# golden_arduino.net
KiCad netlist of a schematic drawn in Altium Designer
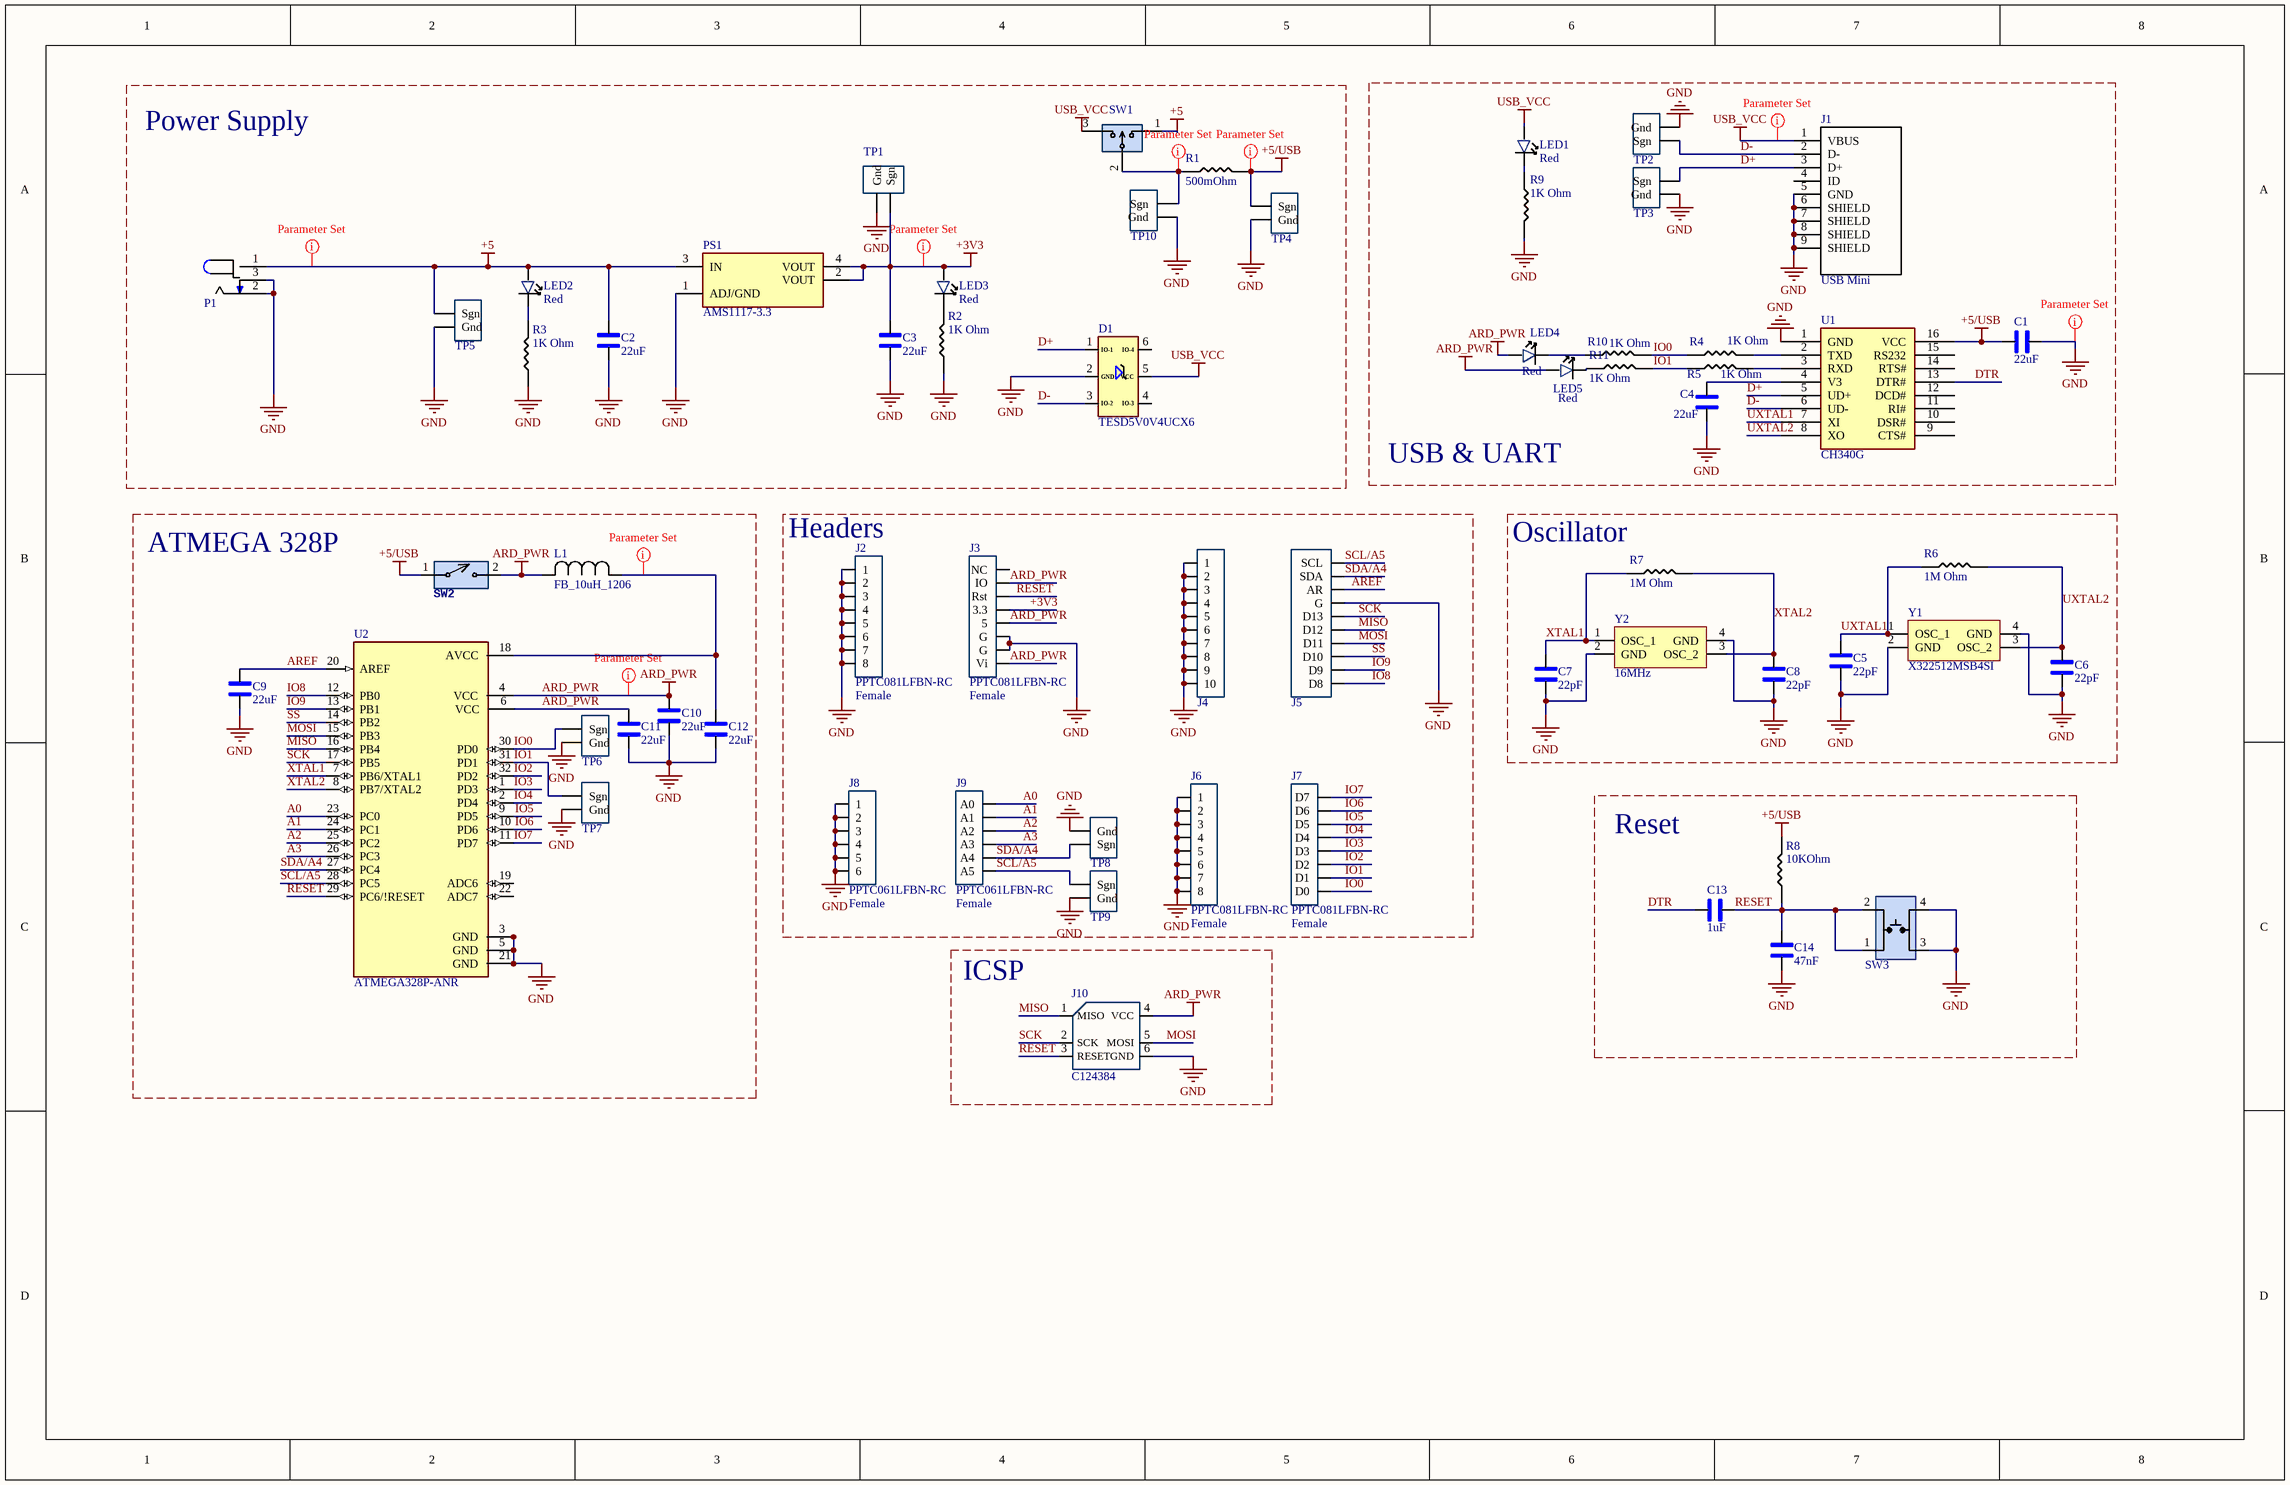
[diagram p0: golden_arduino.SchDoc]

(export (version "E")
  (design (tool "Eeschema 10.0.6"))
  (components
    (comp (ref "C1")
      (value "22uF")
      (footprint "1206_Passive_Capacitor")
      (description "22uF ±10% 25V X5R 1206 Multilayer Ceramic Capacitors MLCC - SMD/SMT RoHS")
      (fields (field (name "MFR PART #") "CL31A226KAHNNNE") (field (name "LCSC PART#") "C12891"))
      (libsource (lib "ECEN5730Lib_2023_05_DS") (part "C_22uF_1206"))
    )
    (comp (ref "C2")
      (value "22uF")
      (footprint "1206_Passive_Capacitor")
      (description "22uF ±10% 25V X5R 1206 Multilayer Ceramic Capacitors MLCC - SMD/SMT RoHS")
      (fields (field (name "MFR PART #") "CL31A226KAHNNNE") (field (name "LCSC PART#") "C12891"))
      (libsource (lib "ECEN5730Lib_2023_05_DS") (part "C_22uF_1206"))
    )
    (comp (ref "C3")
      (value "22uF")
      (footprint "1206_Passive_Capacitor")
      (description "22uF ±10% 25V X5R 1206 Multilayer Ceramic Capacitors MLCC - SMD/SMT RoHS")
      (fields (field (name "MFR PART #") "CL31A226KAHNNNE") (field (name "LCSC PART#") "C12891"))
      (libsource (lib "ECEN5730Lib_2023_05_DS") (part "C_22uF_1206"))
    )
    (comp (ref "C4")
      (value "22uF")
      (footprint "1206_Passive_Capacitor")
      (description "22uF ±10% 25V X5R 1206 Multilayer Ceramic Capacitors MLCC - SMD/SMT RoHS")
      (fields (field (name "MFR PART #") "CL31A226KAHNNNE") (field (name "LCSC PART#") "C12891"))
      (libsource (lib "ECEN5730Lib_2023_05_DS") (part "C_22uF_1206"))
    )
    (comp (ref "C5")
      (value "22pF")
      (footprint "1206_Passive_Capacitor")
      (description "22pF ±5% 1kV C0G 1206 Multilayer Ceramic Capacitors MLCC - SMD/SMT RoHS")
      (fields (field (name "LCSC PART#") "C107174") (field (name "MFR PART #") "CC1206JKNPOCBN220"))
      (libsource (lib "ECEN5730Lib_2023_05_DS") (part "C_22pF_1206"))
    )
    (comp (ref "C6")
      (value "22pF")
      (footprint "1206_Passive_Capacitor")
      (description "22pF ±5% 1kV C0G 1206 Multilayer Ceramic Capacitors MLCC - SMD/SMT RoHS")
      (fields (field (name "LCSC PART#") "C107174") (field (name "MFR PART #") "CC1206JKNPOCBN220"))
      (libsource (lib "ECEN5730Lib_2023_05_DS") (part "C_22pF_1206"))
    )
    (comp (ref "C7")
      (value "22pF")
      (footprint "1206_Passive_Capacitor")
      (description "22pF ±5% 1kV C0G 1206 Multilayer Ceramic Capacitors MLCC - SMD/SMT RoHS")
      (fields (field (name "LCSC PART#") "C107174") (field (name "MFR PART #") "CC1206JKNPOCBN220"))
      (libsource (lib "ECEN5730Lib_2023_05_DS") (part "C_22pF_1206"))
    )
    (comp (ref "C8")
      (value "22pF")
      (footprint "1206_Passive_Capacitor")
      (description "22pF ±5% 1kV C0G 1206 Multilayer Ceramic Capacitors MLCC - SMD/SMT RoHS")
      (fields (field (name "LCSC PART#") "C107174") (field (name "MFR PART #") "CC1206JKNPOCBN220"))
      (libsource (lib "ECEN5730Lib_2023_05_DS") (part "C_22pF_1206"))
    )
    (comp (ref "C9")
      (value "22uF")
      (footprint "1206_Passive_Capacitor")
      (description "22uF ±10% 25V X5R 1206 Multilayer Ceramic Capacitors MLCC - SMD/SMT RoHS")
      (fields (field (name "MFR PART #") "CL31A226KAHNNNE") (field (name "LCSC PART#") "C12891"))
      (libsource (lib "ECEN5730Lib_2023_05_DS") (part "C_22uF_1206"))
    )
    (comp (ref "C10")
      (value "22uF")
      (footprint "1206_Passive_Capacitor")
      (description "22uF ±10% 25V X5R 1206 Multilayer Ceramic Capacitors MLCC - SMD/SMT RoHS")
      (fields (field (name "MFR PART #") "CL31A226KAHNNNE") (field (name "LCSC PART#") "C12891"))
      (libsource (lib "ECEN5730Lib_2023_05_DS") (part "C_22uF_1206"))
    )
    (comp (ref "C11")
      (value "22uF")
      (footprint "1206_Passive_Capacitor")
      (description "22uF ±10% 25V X5R 1206 Multilayer Ceramic Capacitors MLCC - SMD/SMT RoHS")
      (fields (field (name "MFR PART #") "CL31A226KAHNNNE") (field (name "LCSC PART#") "C12891"))
      (libsource (lib "ECEN5730Lib_2023_05_DS") (part "C_22uF_1206"))
    )
    (comp (ref "C12")
      (value "22uF")
      (footprint "1206_Passive_Capacitor")
      (description "22uF ±10% 25V X5R 1206 Multilayer Ceramic Capacitors MLCC - SMD/SMT RoHS")
      (fields (field (name "MFR PART #") "CL31A226KAHNNNE") (field (name "LCSC PART#") "C12891"))
      (libsource (lib "ECEN5730Lib_2023_05_DS") (part "C_22uF_1206"))
    )
    (comp (ref "C13")
      (value "1uF")
      (footprint "1206_Passive_Capacitor")
      (description "MULTILAYER CERAMIC CAPACITORS MLCC - SMD/SMT 1UF 50V 1206 ROHS")
      (fields (field (name "MFR PART #") "CL31B105KBHNNNE") (field (name "LCSC PART#") "C1848"))
      (libsource (lib "ECEN5730Lib_2023_05_DS") (part "C_1uF_1206"))
    )
    (comp (ref "C14")
      (value "47nF")
      (footprint "1206_Passive_Capacitor")
      (description "47nF ±5% 50V C0G 1206 Multilayer Ceramic Capacitors MLCC - SMD/SMT RoHS")
      (fields (field (name "LCSC PART#") "C21812") (field (name "MFR PART #") "GRM31M5C1H473JA01L"))
      (libsource (lib "ECEN5730Lib_2023_05_DS") (part "C_47nF_1206"))
    )
    (comp (ref "D1")
      (value "TESD5V0V4UCX6")
      (footprint "TVS - TESD")
      (description "TVS SOT-23 ROHS")
      (fields (field (name "LCSC PART#") "C5289077"))
      (libsource (lib "ECEN5730Lib_2023_05_DS_NEW") (part "D_TVS_Diode_TESD"))
    )
    (comp (ref "J1")
      (value "USB Mini")
      (footprint "USB_MINI_B")
      (description "Through Hole USB Connectors RoHS")
      (fields (field (name "LCSC PART#") "C46398") (field (name "MFR PART #") "920-462A2021D10102"))
      (libsource (lib "ECEN5730Lib_2023_05_DS") (part "J_USB_B_Mini"))
    )
    (comp (ref "J2")
      (value "PPTC081LFBN-RC")
      (footprint "8_PIN_100MIL - Female")
      (description "8 Position Header Connector 0.100\" (2.54mm) Through Hole Tin")
      (fields (field (name "LCSC PART#") "C27438") (field (name "ALTIUM_VALUE") "Female"))
      (libsource (lib "ECEN5730Lib_2023_05_DS") (part "JF_8_PIN_FEMALE"))
    )
    (comp (ref "J3")
      (value "PPTC081LFBN-RC")
      (footprint "8_PIN_ARD-PWR_100MIL")
      (description "8 Position Header Connector 0.100\" (2.54mm) Through Hole Tin")
      (fields (field (name "LCSC PART#") "C27438") (field (name "ALTIUM_VALUE") "Female"))
      (libsource (lib "ECEN5730Lib_2023_05_DS") (part "JF_8_PIN_FEMA_ARD-Pwr"))
    )
    (comp (ref "J4")
      (value "PPTC101LFBN-RC")
      (footprint "10_PIN_100MIL - Female")
      (description "10 Position Header Connector 0.100\" (2.54mm) Through Hole Tin")
      (fields (field (name "LCSC PART#") "C225507"))
      (libsource (lib "ECEN5730Lib_2023_05_DS") (part "JF_10_PIN_FEMALE_"))
    )
    (comp (ref "J5")
      (value "PPTC101LFBN-RC")
      (footprint "10_PIN_ARDUINO_100MIL")
      (description "10 Position Header Connector 0.100\" (2.54mm) Through Hole Tin")
      (fields (field (name "LCSC PART#") "C225507"))
      (libsource (lib "ECEN5730Lib_2023_05_DS") (part "JF_10_PIN_FEMA_ARDUINO"))
    )
    (comp (ref "J6")
      (value "PPTC081LFBN-RC")
      (footprint "8_PIN_100MIL - Female")
      (description "8 Position Header Connector 0.100\" (2.54mm) Through Hole Tin")
      (fields (field (name "LCSC PART#") "C27438") (field (name "ALTIUM_VALUE") "Female"))
      (libsource (lib "ECEN5730Lib_2023_05_DS") (part "JF_8_PIN_FEMALE"))
    )
    (comp (ref "J7")
      (value "PPTC081LFBN-RC")
      (footprint "8_PIN_ARD-DIG_100MIL")
      (description "8 Position Header Connector 0.100\" (2.54mm) Through Hole Tin")
      (fields (field (name "LCSC PART#") "C27438") (field (name "ALTIUM_VALUE") "Female"))
      (libsource (lib "ECEN5730Lib_2023_05_DS") (part "JF_8_PIN_FEMA_ARD-Dig"))
    )
    (comp (ref "J8")
      (value "PPTC061LFBN-RC")
      (footprint "6_PIN_100MIL -Female")
      (description "6 Position Header Connector 0.100\" (2.54mm) Through Hole Tin")
      (fields (field (name "LCSC PART#") "C40877") (field (name "ALTIUM_VALUE") "Female"))
      (libsource (lib "ECEN5730Lib_2023_05_DS") (part "JF_6_PIN_FEMALE"))
    )
    (comp (ref "J9")
      (value "PPTC061LFBN-RC")
      (footprint "6_PIN_ARD-Analog_100mil")
      (description "6 Position Header Connector 0.100\" (2.54mm) Through Hole Tin")
      (fields (field (name "LCSC PART#") "C40877") (field (name "ALTIUM_VALUE") "Female"))
      (libsource (lib "ECEN5730Lib_2023_05_DS") (part "JF_6_PIN_FEMA_ARD-Anolog"))
    )
    (comp (ref "J10")
      (value "NRPN032PAEN-RC")
      (footprint "ICSP")
      (description "Connector Header Through Hole 6 position 0.079\" (2.00mm)")
      (fields (field (name "LCSC PART#") "C124384"))
      (libsource (lib "ECEN5730Lib_2023_05_DS") (part "J_ICSP"))
    )
    (comp (ref "L1")
      (value "FB_10uH_1206")
      (footprint "AIML-1206_ABR-M")
      (description "25mA 10uH ±10% 800mΩ 1206  Inductors (SMD) ROHS")
      (fields (field (name "MFR PART #") "CMI321609X100KT") (field (name "LCSC PART#") "C1051"))
      (libsource (lib "ECEN5730Lib_2023_05_DS") (part "FB_10uH_1206"))
    )
    (comp (ref "LED1")
      (value "Red")
      (footprint "LED_1206")
      (description "Red 621~631nm 1206 Light Emitting Diodes (LED) RoHS")
      (fields (field (name "MFR PART #") "15-21/R6C-FQ1R1B/2T") (field (name "LCSC PART#") "C93133"))
      (libsource (lib "ECEN5730Lib_2023_05_DS") (part "LED_RED_1206"))
    )
    (comp (ref "LED2")
      (value "Red")
      (footprint "LED_1206")
      (description "Red 621~631nm 1206 Light Emitting Diodes (LED) RoHS")
      (fields (field (name "MFR PART #") "15-21/R6C-FQ1R1B/2T") (field (name "LCSC PART#") "C93133"))
      (libsource (lib "ECEN5730Lib_2023_05_DS") (part "LED_RED_1206"))
    )
    (comp (ref "LED3")
      (value "Red")
      (footprint "LED_1206")
      (description "Red 621~631nm 1206 Light Emitting Diodes (LED) RoHS")
      (fields (field (name "MFR PART #") "15-21/R6C-FQ1R1B/2T") (field (name "LCSC PART#") "C93133"))
      (libsource (lib "ECEN5730Lib_2023_05_DS") (part "LED_RED_1206"))
    )
    (comp (ref "LED4")
      (value "Red")
      (footprint "LED_1206")
      (description "Red 621~631nm 1206 Light Emitting Diodes (LED) RoHS")
      (fields (field (name "MFR PART #") "15-21/R6C-FQ1R1B/2T") (field (name "LCSC PART#") "C93133"))
      (libsource (lib "ECEN5730Lib_2023_05_DS") (part "LED_RED_1206"))
    )
    (comp (ref "LED5")
      (value "Red")
      (footprint "LED_1206")
      (description "Red 621~631nm 1206 Light Emitting Diodes (LED) RoHS")
      (fields (field (name "MFR PART #") "15-21/R6C-FQ1R1B/2T") (field (name "LCSC PART#") "C93133"))
      (libsource (lib "ECEN5730Lib_2023_05_DS") (part "LED_RED_1206"))
    )
    (comp (ref "P1")
      (value "Power Jack")
      (footprint "Power_Jack")
      (description "Power Barrel Connector Jack 2.10mm ID (0.083\"), 5.50mm OD (0.217\") Through Hole, Right Angle")
      (fields (field (name "MFR PART #") "PJ-102A") (field (name "LCSC PART#") "C136744"))
      (libsource (lib "ECEN5730Lib_2023_05_DS") (part "P_Power Jack"))
    )
    (comp (ref "PS1")
      (value "AMS1117-3.3")
      (footprint "LDO")
      (description "LOW DROPOUT REGULATORS(LDO) POSITIVE FIXED 1.3V @ 800MA 15V 3.3V 1A SOT-223 ROHS")
      (fields (field (name "LCSC PART#") "C6186"))
      (libsource (lib "ECEN5730Lib_2023_05_DS") (part "PS_AMS_LDO_3v3"))
    )
    (comp (ref "R1")
      (value "500mOhm")
      (footprint "1206_Passive_Resitor")
      (description "Resistors/Shunt 250mW 500mΩ ±800ppm/℃ ±5% 1206  Current Sense  Resistors ROHS")
      (fields (field (name "MFR PART #") "1206W4J050KT5E") (field (name "LCSC PART#") "C247433"))
      (libsource (lib "ECEN5730Lib_2023_05_DS") (part "R_500mOhm_1206"))
    )
    (comp (ref "R2")
      (value "1K Ohm")
      (footprint "1206_Passive_Resitor")
      (description "CHIP RESISTOR - SURFACE MOUNT 1KOHMS ±1% 1/4W 1206 ROHS")
      (fields (field (name "MFR PART #") "RNCP1206FTD1K00CT") (field (name "LCSC PART#") "C4410"))
      (libsource (lib "ECEN5730Lib_2023_05_DS") (part "R_1K_1206"))
    )
    (comp (ref "R3")
      (value "1K Ohm")
      (footprint "1206_Passive_Resitor")
      (description "CHIP RESISTOR - SURFACE MOUNT 1KOHMS ±1% 1/4W 1206 ROHS")
      (fields (field (name "MFR PART #") "RNCP1206FTD1K00CT") (field (name "LCSC PART#") "C4410"))
      (libsource (lib "ECEN5730Lib_2023_05_DS") (part "R_1K_1206"))
    )
    (comp (ref "R4")
      (value "1K Ohm")
      (footprint "1206_Passive_Resitor")
      (description "CHIP RESISTOR - SURFACE MOUNT 1KOHMS ±1% 1/4W 1206 ROHS")
      (fields (field (name "MFR PART #") "RNCP1206FTD1K00CT") (field (name "LCSC PART#") "C4410"))
      (libsource (lib "ECEN5730Lib_2023_05_DS") (part "R_1K_1206"))
    )
    (comp (ref "R5")
      (value "1K Ohm")
      (footprint "1206_Passive_Resitor")
      (description "CHIP RESISTOR - SURFACE MOUNT 1KOHMS ±1% 1/4W 1206 ROHS")
      (fields (field (name "MFR PART #") "RNCP1206FTD1K00CT") (field (name "LCSC PART#") "C4410"))
      (libsource (lib "ECEN5730Lib_2023_05_DS") (part "R_1K_1206"))
    )
    (comp (ref "R6")
      (value "1M Ohm")
      (footprint "1206_Passive_Resitor")
      (description "CHIP RESISTOR - SURFACE MOUNT 1MOHMS ±1% 1/4W 1206 ROHS")
      (fields (field (name "MFR PART #") "RMCF1206JT1M00") (field (name "LCSC PART#") "C17927"))
      (libsource (lib "ECEN5730Lib_2023_05_DS") (part "R_1M_1206"))
    )
    (comp (ref "R7")
      (value "1M Ohm")
      (footprint "1206_Passive_Resitor")
      (description "CHIP RESISTOR - SURFACE MOUNT 1MOHMS ±1% 1/4W 1206 ROHS")
      (fields (field (name "MFR PART #") "RMCF1206JT1M00") (field (name "LCSC PART#") "C17927"))
      (libsource (lib "ECEN5730Lib_2023_05_DS") (part "R_1M_1206"))
    )
    (comp (ref "R8")
      (value "10KOhm")
      (footprint "1206_Passive_Resitor")
      (description "10 kOhms ±5% 0.25W, 1/4W Chip Resistor 1206 (3216 Metric) Automotive AEC-Q200 Thick Film")
      (fields (field (name "MFR PART #") "RMCF1206FT10K0") (field (name "LCSC PART#") "C17902"))
      (libsource (lib "ECEN5730Lib_2023_05_DS") (part "R_10KOhm_1206"))
    )
    (comp (ref "R9")
      (value "1K Ohm")
      (footprint "1206_Passive_Resitor")
      (description "CHIP RESISTOR - SURFACE MOUNT 1KOHMS ±1% 1/4W 1206 ROHS")
      (fields (field (name "MFR PART #") "RNCP1206FTD1K00CT") (field (name "LCSC PART#") "C4410"))
      (libsource (lib "ECEN5730Lib_2023_05_DS") (part "R_1K_1206"))
    )
    (comp (ref "R10")
      (value "1K Ohm")
      (footprint "1206_Passive_Resitor")
      (description "CHIP RESISTOR - SURFACE MOUNT 1KOHMS ±1% 1/4W 1206 ROHS")
      (fields (field (name "MFR PART #") "RNCP1206FTD1K00CT") (field (name "LCSC PART#") "C4410"))
      (libsource (lib "ECEN5730Lib_2023_05_DS") (part "R_1K_1206"))
    )
    (comp (ref "R11")
      (value "1K Ohm")
      (footprint "1206_Passive_Resitor")
      (description "CHIP RESISTOR - SURFACE MOUNT 1KOHMS ±1% 1/4W 1206 ROHS")
      (fields (field (name "MFR PART #") "RNCP1206FTD1K00CT") (field (name "LCSC PART#") "C4410"))
      (libsource (lib "ECEN5730Lib_2023_05_DS") (part "R_1K_1206"))
    )
    (comp (ref "SW1")
      (value "PREC003SAAN-RC")
      (footprint "3_PIN_100mil")
      (description "Connector Header Through Hole 3 position 0.100\" (2.54mm)")
      (fields (field (name "LCSC PART#") "C49257"))
      (libsource (lib "ECEN5730Lib_2023_05_DS") (part "SW_3Pin_100mil_Switch"))
    )
    (comp (ref "SW2")
      (value "SW_2Pin_100mil_Switch")
      (footprint "2Pin-Header-Conn")
      (description "2Pin Header")
      (fields (field (name "LCSC PART#") "C124375"))
      (libsource (lib "ECEN5730Lib_2023_05_DS") (part "SW_2Pin_100mil_Switch"))
    )
    (comp (ref "SW3")
      (value "TL3305AF160QG")
      (footprint "Switch_JLC")
      (description "Tactile Switch SPST-NO Top Actuated Surface Mount")
      (fields (field (name "MFR PART #") "KH-4.5X4.5X4.3H-STM") (field (name "LCSC PART#") "C2837550"))
      (libsource (lib "ECEN5730Lib_2023_05_DS") (part "SW_Push_Button_JLC"))
    )
    (comp (ref "TP1")
      (value "10x Probe TP")
      (footprint "TP10x_Probe")
      (description "Test Point 300 mil centers")
      (libsource (lib "ECEN5730Lib_2023_05_DS") (part "TP_10x_Probe"))
    )
    (comp (ref "TP2")
      (value "10x Probe TP")
      (footprint "TP10x_Probe")
      (description "Test Point 300 mil centers")
      (libsource (lib "") (part "TP_10x_Probe_2"))
    )
    (comp (ref "TP3")
      (value "10x Probe TP")
      (footprint "TP10x_Probe")
      (description "Test Point 300 mil centers")
      (libsource (lib "") (part "TP_10x_Probe_3"))
    )
    (comp (ref "TP4")
      (value "10x Probe TP")
      (footprint "TP10x_Probe")
      (description "Test Point 300 mil centers")
      (libsource (lib "ECEN5730Lib_2023_05_DS") (part "TP_10x_Probe"))
    )
    (comp (ref "TP5")
      (value "10x Probe TP")
      (footprint "TP10x_Probe")
      (description "Test Point 300 mil centers")
      (libsource (lib "ECEN5730Lib_2023_05_DS") (part "TP_10x_Probe"))
    )
    (comp (ref "TP6")
      (value "10x Probe TP")
      (footprint "TP10x_Probe")
      (description "Test Point 300 mil centers")
      (libsource (lib "ECEN5730Lib_2023_05_DS") (part "TP_10x_Probe"))
    )
    (comp (ref "TP7")
      (value "10x Probe TP")
      (footprint "TP10x_Probe")
      (description "Test Point 300 mil centers")
      (libsource (lib "ECEN5730Lib_2023_05_DS") (part "TP_10x_Probe"))
    )
    (comp (ref "TP8")
      (value "10x Probe TP")
      (footprint "TP10x_Probe")
      (description "Test Point 300 mil centers")
      (libsource (lib "") (part "TP_10x_Probe_1"))
    )
    (comp (ref "TP9")
      (value "10x Probe TP")
      (footprint "TP10x_Probe")
      (description "Test Point 300 mil centers")
      (libsource (lib "ECEN5730Lib_2023_05_DS") (part "TP_10x_Probe"))
    )
    (comp (ref "TP10")
      (value "10x Probe TP")
      (footprint "TP10x_Probe")
      (description "Test Point 300 mil centers")
      (libsource (lib "") (part "TP_10x_Probe_3"))
    )
    (comp (ref "U1")
      (value "CH340G")
      (footprint "USB to serial")
      (description "Transceiver USB 2.0 2Mbps SOP-16_150mil USB ICs RoHS")
      (fields (field (name "LCSC PART#") "C14267"))
      (libsource (lib "ECEN5730Lib_2023_05_DS") (part "U_USBtoSerial"))
    )
    (comp (ref "U2")
      (value "ATMEGA328P-ANR")
      (footprint "ATMega328P")
      (description "AVR AVR® ATmega Microcontroller IC 8-Bit 20MHz 32KB (16K x 16) FLASH 32-TQFP (7x7)")
      (fields (field (name "MFR PART #") "ATMEGA328P-AU") (field (name "LCSC PART#") "C14877"))
      (libsource (lib "ECEN5730Lib_2023_05_DS") (part "U_ATMega328P"))
    )
    (comp (ref "Y1")
      (value "X322512MSB4SI")
      (footprint "Crystal resonator")
      (description "SMD Crystal Resonators 12MHz ±10ppm SMD-3225_4P RoHS")
      (fields (field (name "LCSC PART#") "C9002"))
      (libsource (lib "ECEN5730Lib_2023_05_DS") (part "X_12MHz_Res"))
    )
    (comp (ref "Y2")
      (value "16MHz")
      (footprint "Crystal resonator")
      (description "±10ppm 16000000Hz -40℃~85℃ 贴片无源晶振 60Ω 9pF SMD3225-4P Crystals ROHS")
      (fields (field (name "LCSC PART#") "C13738") (field (name "MFR PART #") "X322516MLB4SI"))
      (libsource (lib "ECEN5730Lib_2023_05_DS") (part "X_16Mhz_Res"))
    )
  )
  (nets
    (net (code "1") (name "+3V3") (class "Default")
      (node (ref "C3") (pin "2") (pinfunction "2_2") (pintype "passive"))
      (node (ref "J3") (pin "4") (pinfunction "3.3_4") (pintype "passive"))
      (node (ref "LED3") (pin "1") (pinfunction "1_1") (pintype "passive"))
      (node (ref "PS1") (pin "2") (pinfunction "VOUT_2") (pintype "power_in"))
      (node (ref "PS1") (pin "4") (pinfunction "VOUT_4") (pintype "power_in"))
      (node (ref "TP1") (pin "1") (pinfunction "Sgn_1") (pintype "passive"))
    )
    (net (code "2") (name "+5") (class "Default")
      (node (ref "C2") (pin "2") (pinfunction "2_2") (pintype "passive"))
      (node (ref "LED2") (pin "1") (pinfunction "1_1") (pintype "passive"))
      (node (ref "P1") (pin "1") (pinfunction "1_1") (pintype "power_in"))
      (node (ref "PS1") (pin "3") (pinfunction "IN_3") (pintype "power_in"))
      (node (ref "SW1") (pin "1") (pinfunction "1_1") (pintype "passive"))
      (node (ref "TP5") (pin "1") (pinfunction "Sgn_1") (pintype "passive"))
    )
    (net (code "3") (name "+5{slash}USB") (class "Default")
      (node (ref "C1") (pin "1") (pinfunction "1_1") (pintype "passive"))
      (node (ref "R1") (pin "2") (pinfunction "2_2") (pintype "passive"))
      (node (ref "R8") (pin "2") (pinfunction "2_2") (pintype "passive"))
      (node (ref "SW2") (pin "1") (pinfunction "1_1") (pintype "passive"))
      (node (ref "TP4") (pin "1") (pinfunction "Sgn_1") (pintype "passive"))
      (node (ref "U1") (pin "16") (pinfunction "VCC_16") (pintype "passive"))
    )
    (net (code "4") (name "/A0") (class "Default")
      (node (ref "J9") (pin "1") (pinfunction "A0_1") (pintype "passive"))
      (node (ref "U2") (pin "23") (pinfunction "PC0_23") (pintype "bidirectional"))
    )
    (net (code "5") (name "/A1") (class "Default")
      (node (ref "J9") (pin "2") (pinfunction "A1_2") (pintype "passive"))
      (node (ref "U2") (pin "24") (pinfunction "PC1_24") (pintype "bidirectional"))
    )
    (net (code "6") (name "/A2") (class "Default")
      (node (ref "J9") (pin "3") (pinfunction "A2_3") (pintype "passive"))
      (node (ref "U2") (pin "25") (pinfunction "PC2_25") (pintype "bidirectional"))
    )
    (net (code "7") (name "/A3") (class "Default")
      (node (ref "J9") (pin "4") (pinfunction "A3_4") (pintype "passive"))
      (node (ref "U2") (pin "26") (pinfunction "PC3_26") (pintype "bidirectional"))
    )
    (net (code "8") (name "/AREF") (class "Default")
      (node (ref "C9") (pin "1") (pinfunction "1_1") (pintype "passive"))
      (node (ref "J5") (pin "3") (pinfunction "AR_3") (pintype "passive"))
      (node (ref "U2") (pin "20") (pinfunction "AREF_20") (pintype "input"))
    )
    (net (code "9") (name "/D+") (class "Default")
      (node (ref "D1") (pin "1") (pinfunction "IO-1_1") (pintype "passive"))
      (node (ref "J1") (pin "3") (pinfunction "D+_3") (pintype "passive"))
      (node (ref "TP3") (pin "1") (pinfunction "Sgn_1") (pintype "passive"))
      (node (ref "U1") (pin "5") (pinfunction "UD+_5") (pintype "passive"))
    )
    (net (code "10") (name "/D-") (class "Default")
      (node (ref "D1") (pin "3") (pinfunction "IO-2_3") (pintype "passive"))
      (node (ref "J1") (pin "2") (pinfunction "D-_2") (pintype "passive"))
      (node (ref "TP2") (pin "1") (pinfunction "Sgn_1") (pintype "passive"))
      (node (ref "U1") (pin "6") (pinfunction "UD-_6") (pintype "passive"))
    )
    (net (code "11") (name "/DTR") (class "Default")
      (node (ref "C13") (pin "1") (pinfunction "1_1") (pintype "passive"))
      (node (ref "U1") (pin "13") (pinfunction "DTR#_13") (pintype "passive"))
    )
    (net (code "12") (name "/IO0") (class "Default")
      (node (ref "J7") (pin "8") (pinfunction "D0_8") (pintype "passive"))
      (node (ref "R10") (pin "2") (pinfunction "2_2") (pintype "passive"))
      (node (ref "R4") (pin "1") (pinfunction "1_1") (pintype "passive"))
      (node (ref "TP6") (pin "1") (pinfunction "Sgn_1") (pintype "passive"))
      (node (ref "U2") (pin "30") (pinfunction "PD0_30") (pintype "bidirectional"))
    )
    (net (code "13") (name "/IO1") (class "Default")
      (node (ref "J7") (pin "7") (pinfunction "D1_7") (pintype "passive"))
      (node (ref "R11") (pin "2") (pinfunction "2_2") (pintype "passive"))
      (node (ref "R5") (pin "1") (pinfunction "1_1") (pintype "passive"))
      (node (ref "TP7") (pin "1") (pinfunction "Sgn_1") (pintype "passive"))
      (node (ref "U2") (pin "31") (pinfunction "PD1_31") (pintype "bidirectional"))
    )
    (net (code "14") (name "/IO2") (class "Default")
      (node (ref "J7") (pin "6") (pinfunction "D2_6") (pintype "passive"))
      (node (ref "U2") (pin "32") (pinfunction "PD2_32") (pintype "bidirectional"))
    )
    (net (code "15") (name "/IO3") (class "Default")
      (node (ref "J7") (pin "5") (pinfunction "D3_5") (pintype "passive"))
      (node (ref "U2") (pin "1") (pinfunction "PD3_1") (pintype "bidirectional"))
    )
    (net (code "16") (name "/IO4") (class "Default")
      (node (ref "J7") (pin "4") (pinfunction "D4_4") (pintype "passive"))
      (node (ref "U2") (pin "2") (pinfunction "PD4_2") (pintype "bidirectional"))
    )
    (net (code "17") (name "/IO5") (class "Default")
      (node (ref "J7") (pin "3") (pinfunction "D5_3") (pintype "passive"))
      (node (ref "U2") (pin "9") (pinfunction "PD5_9") (pintype "bidirectional"))
    )
    (net (code "18") (name "/IO6") (class "Default")
      (node (ref "J7") (pin "2") (pinfunction "D6_2") (pintype "passive"))
      (node (ref "U2") (pin "10") (pinfunction "PD6_10") (pintype "bidirectional"))
    )
    (net (code "19") (name "/IO7") (class "Default")
      (node (ref "J7") (pin "1") (pinfunction "D7_1") (pintype "passive"))
      (node (ref "U2") (pin "11") (pinfunction "PD7_11") (pintype "bidirectional"))
    )
    (net (code "20") (name "/IO8") (class "Default")
      (node (ref "J5") (pin "10") (pinfunction "D8_10") (pintype "passive"))
      (node (ref "U2") (pin "12") (pinfunction "PB0_12") (pintype "bidirectional"))
    )
    (net (code "21") (name "/IO9") (class "Default")
      (node (ref "J5") (pin "9") (pinfunction "D9_9") (pintype "passive"))
      (node (ref "U2") (pin "13") (pinfunction "PB1_13") (pintype "bidirectional"))
    )
    (net (code "22") (name "/MISO") (class "Default")
      (node (ref "J10") (pin "1") (pinfunction "MISO_1") (pintype "passive"))
      (node (ref "J5") (pin "6") (pinfunction "D12_6") (pintype "passive"))
      (node (ref "U2") (pin "16") (pinfunction "PB4_16") (pintype "bidirectional"))
    )
    (net (code "23") (name "/MOSI") (class "Default")
      (node (ref "J10") (pin "5") (pinfunction "MOSI_5") (pintype "passive"))
      (node (ref "J5") (pin "7") (pinfunction "D11_7") (pintype "passive"))
      (node (ref "U2") (pin "15") (pinfunction "PB3_15") (pintype "bidirectional"))
    )
    (net (code "24") (name "/RESET") (class "Default")
      (node (ref "C13") (pin "2") (pinfunction "2_2") (pintype "passive"))
      (node (ref "C14") (pin "2") (pinfunction "2_2") (pintype "passive"))
      (node (ref "J10") (pin "3") (pinfunction "RESET_3") (pintype "passive"))
      (node (ref "J3") (pin "3") (pinfunction "Rst_3") (pintype "passive"))
      (node (ref "R8") (pin "1") (pinfunction "1_1") (pintype "passive"))
      (node (ref "SW3") (pin "1") (pinfunction "1_1") (pintype "passive"))
      (node (ref "SW3") (pin "2") (pinfunction "2_2") (pintype "passive"))
      (node (ref "U2") (pin "29") (pinfunction "PC6/!RESET_29") (pintype "bidirectional"))
    )
    (net (code "25") (name "/SCK") (class "Default")
      (node (ref "J10") (pin "2") (pinfunction "SCK_2") (pintype "passive"))
      (node (ref "J5") (pin "5") (pinfunction "D13_5") (pintype "passive"))
      (node (ref "U2") (pin "17") (pinfunction "PB5_17") (pintype "bidirectional"))
    )
    (net (code "26") (name "/SCL{slash}A5") (class "Default")
      (node (ref "J5") (pin "1") (pinfunction "SCL_1") (pintype "passive"))
      (node (ref "J9") (pin "6") (pinfunction "A5_6") (pintype "passive"))
      (node (ref "TP9") (pin "1") (pinfunction "Sgn_1") (pintype "passive"))
      (node (ref "U2") (pin "28") (pinfunction "PC5_28") (pintype "bidirectional"))
    )
    (net (code "27") (name "/SDA{slash}A4") (class "Default")
      (node (ref "J5") (pin "2") (pinfunction "SDA_2") (pintype "passive"))
      (node (ref "J9") (pin "5") (pinfunction "A4_5") (pintype "passive"))
      (node (ref "TP8") (pin "1") (pinfunction "Sgn_1") (pintype "passive"))
      (node (ref "U2") (pin "27") (pinfunction "PC4_27") (pintype "bidirectional"))
    )
    (net (code "28") (name "/SS") (class "Default")
      (node (ref "J5") (pin "8") (pinfunction "D10_8") (pintype "passive"))
      (node (ref "U2") (pin "14") (pinfunction "PB2_14") (pintype "bidirectional"))
    )
    (net (code "29") (name "/UXTAL1") (class "Default")
      (node (ref "C5") (pin "2") (pinfunction "2_2") (pintype "passive"))
      (node (ref "R6") (pin "1") (pinfunction "1_1") (pintype "passive"))
      (node (ref "U1") (pin "7") (pinfunction "XI_7") (pintype "passive"))
      (node (ref "Y1") (pin "1") (pinfunction "OSC_1_1") (pintype "passive"))
    )
    (net (code "30") (name "/UXTAL2") (class "Default")
      (node (ref "C6") (pin "2") (pinfunction "2_2") (pintype "passive"))
      (node (ref "R6") (pin "2") (pinfunction "2_2") (pintype "passive"))
      (node (ref "U1") (pin "8") (pinfunction "XO_8") (pintype "passive"))
      (node (ref "Y1") (pin "3") (pinfunction "OSC_2_3") (pintype "passive"))
    )
    (net (code "31") (name "/XTAL1") (class "Default")
      (node (ref "C7") (pin "2") (pinfunction "2_2") (pintype "passive"))
      (node (ref "R7") (pin "1") (pinfunction "1_1") (pintype "passive"))
      (node (ref "U2") (pin "7") (pinfunction "PB6/XTAL1_7") (pintype "bidirectional"))
      (node (ref "Y2") (pin "1") (pinfunction "OSC_1_1") (pintype "passive"))
    )
    (net (code "32") (name "/XTAL2") (class "Default")
      (node (ref "C8") (pin "2") (pinfunction "2_2") (pintype "passive"))
      (node (ref "R7") (pin "2") (pinfunction "2_2") (pintype "passive"))
      (node (ref "U2") (pin "8") (pinfunction "PB7/XTAL2_8") (pintype "bidirectional"))
      (node (ref "Y2") (pin "3") (pinfunction "OSC_2_3") (pintype "passive"))
    )
    (net (code "33") (name "ARD_PWR") (class "Default")
      (node (ref "C10") (pin "1") (pinfunction "1_1") (pintype "passive"))
      (node (ref "C11") (pin "1") (pinfunction "1_1") (pintype "passive"))
      (node (ref "J10") (pin "4") (pinfunction "VCC_4") (pintype "passive"))
      (node (ref "J3") (pin "2") (pinfunction "IO_2") (pintype "passive"))
      (node (ref "J3") (pin "5") (pinfunction "5_5") (pintype "passive"))
      (node (ref "J3") (pin "8") (pinfunction "Vi_8") (pintype "passive"))
      (node (ref "L1") (pin "2") (pinfunction "2_2") (pintype "passive"))
      (node (ref "LED4") (pin "1") (pinfunction "1_1") (pintype "passive"))
      (node (ref "LED5") (pin "1") (pinfunction "1_1") (pintype "passive"))
      (node (ref "SW2") (pin "2") (pinfunction "2_2") (pintype "passive"))
      (node (ref "U2") (pin "4") (pinfunction "VCC_4") (pintype "power_in"))
      (node (ref "U2") (pin "6") (pinfunction "VCC_6") (pintype "power_in"))
    )
    (net (code "34") (name "GND") (class "Default")
      (node (ref "C1") (pin "2") (pinfunction "2_2") (pintype "passive"))
      (node (ref "C10") (pin "2") (pinfunction "2_2") (pintype "passive"))
      (node (ref "C11") (pin "2") (pinfunction "2_2") (pintype "passive"))
      (node (ref "C12") (pin "2") (pinfunction "2_2") (pintype "passive"))
      (node (ref "C14") (pin "1") (pinfunction "1_1") (pintype "passive"))
      (node (ref "C2") (pin "1") (pinfunction "1_1") (pintype "passive"))
      (node (ref "C3") (pin "1") (pinfunction "1_1") (pintype "passive"))
      (node (ref "C4") (pin "2") (pinfunction "2_2") (pintype "passive"))
      (node (ref "C5") (pin "1") (pinfunction "1_1") (pintype "passive"))
      (node (ref "C6") (pin "1") (pinfunction "1_1") (pintype "passive"))
      (node (ref "C7") (pin "1") (pinfunction "1_1") (pintype "passive"))
      (node (ref "C8") (pin "1") (pinfunction "1_1") (pintype "passive"))
      (node (ref "C9") (pin "2") (pinfunction "2_2") (pintype "passive"))
      (node (ref "D1") (pin "2") (pinfunction "GND_2") (pintype "passive"))
      (node (ref "J1") (pin "5") (pinfunction "GND_5") (pintype "passive"))
      (node (ref "J1") (pin "6") (pinfunction "SHIELD_6") (pintype "passive"))
      (node (ref "J1") (pin "7") (pinfunction "SHIELD_7") (pintype "passive"))
      (node (ref "J1") (pin "8") (pinfunction "SHIELD_8") (pintype "passive"))
      (node (ref "J1") (pin "9") (pinfunction "SHIELD_9") (pintype "passive"))
      (node (ref "J10") (pin "6") (pinfunction "GND_6") (pintype "passive"))
      (node (ref "J2") (pin "1") (pinfunction "1_1") (pintype "passive"))
      (node (ref "J2") (pin "2") (pinfunction "2_2") (pintype "passive"))
      (node (ref "J2") (pin "3") (pinfunction "3_3") (pintype "passive"))
      (node (ref "J2") (pin "4") (pinfunction "4_4") (pintype "passive"))
      (node (ref "J2") (pin "5") (pinfunction "5_5") (pintype "passive"))
      (node (ref "J2") (pin "6") (pinfunction "6_6") (pintype "passive"))
      (node (ref "J2") (pin "7") (pinfunction "7_7") (pintype "passive"))
      (node (ref "J2") (pin "8") (pinfunction "8_8") (pintype "passive"))
      (node (ref "J3") (pin "6") (pinfunction "G_6") (pintype "passive"))
      (node (ref "J3") (pin "7") (pinfunction "G_7") (pintype "passive"))
      (node (ref "J4") (pin "1") (pinfunction "1_1") (pintype "passive"))
      (node (ref "J4") (pin "10") (pinfunction "10_10") (pintype "passive"))
      (node (ref "J4") (pin "2") (pinfunction "2_2") (pintype "passive"))
      (node (ref "J4") (pin "3") (pinfunction "3_3") (pintype "passive"))
      (node (ref "J4") (pin "4") (pinfunction "4_4") (pintype "passive"))
      (node (ref "J4") (pin "5") (pinfunction "5_5") (pintype "passive"))
      (node (ref "J4") (pin "6") (pinfunction "6_6") (pintype "passive"))
      (node (ref "J4") (pin "7") (pinfunction "7_7") (pintype "passive"))
      (node (ref "J4") (pin "8") (pinfunction "8_8") (pintype "passive"))
      (node (ref "J4") (pin "9") (pinfunction "9_9") (pintype "passive"))
      (node (ref "J5") (pin "4") (pinfunction "G_4") (pintype "passive"))
      (node (ref "J6") (pin "1") (pinfunction "1_1") (pintype "passive"))
      (node (ref "J6") (pin "2") (pinfunction "2_2") (pintype "passive"))
      (node (ref "J6") (pin "3") (pinfunction "3_3") (pintype "passive"))
      (node (ref "J6") (pin "4") (pinfunction "4_4") (pintype "passive"))
      (node (ref "J6") (pin "5") (pinfunction "5_5") (pintype "passive"))
      (node (ref "J6") (pin "6") (pinfunction "6_6") (pintype "passive"))
      (node (ref "J6") (pin "7") (pinfunction "7_7") (pintype "passive"))
      (node (ref "J6") (pin "8") (pinfunction "8_8") (pintype "passive"))
      (node (ref "J8") (pin "1") (pinfunction "1_1") (pintype "passive"))
      (node (ref "J8") (pin "2") (pinfunction "2_2") (pintype "passive"))
      (node (ref "J8") (pin "3") (pinfunction "3_3") (pintype "passive"))
      (node (ref "J8") (pin "4") (pinfunction "4_4") (pintype "passive"))
      (node (ref "J8") (pin "5") (pinfunction "5_5") (pintype "passive"))
      (node (ref "J8") (pin "6") (pinfunction "6_6") (pintype "passive"))
      (node (ref "P1") (pin "2") (pinfunction "2_2") (pintype "power_in"))
      (node (ref "P1") (pin "3") (pinfunction "3_3") (pintype "power_in"))
      (node (ref "PS1") (pin "1") (pinfunction "ADJ/GND_1") (pintype "passive"))
      (node (ref "R2") (pin "1") (pinfunction "1_1") (pintype "passive"))
      (node (ref "R3") (pin "1") (pinfunction "1_1") (pintype "passive"))
      (node (ref "R9") (pin "2") (pinfunction "2_2") (pintype "passive"))
      (node (ref "SW3") (pin "3") (pinfunction "3_3") (pintype "passive"))
      (node (ref "SW3") (pin "4") (pinfunction "4_4") (pintype "passive"))
      (node (ref "TP1") (pin "2") (pinfunction "Gnd_2") (pintype "passive"))
      (node (ref "TP10") (pin "2") (pinfunction "Gnd_2") (pintype "passive"))
      (node (ref "TP2") (pin "2") (pinfunction "Gnd_2") (pintype "passive"))
      (node (ref "TP3") (pin "2") (pinfunction "Gnd_2") (pintype "passive"))
      (node (ref "TP4") (pin "2") (pinfunction "Gnd_2") (pintype "passive"))
      (node (ref "TP5") (pin "2") (pinfunction "Gnd_2") (pintype "passive"))
      (node (ref "TP6") (pin "2") (pinfunction "Gnd_2") (pintype "passive"))
      (node (ref "TP7") (pin "2") (pinfunction "Gnd_2") (pintype "passive"))
      (node (ref "TP8") (pin "2") (pinfunction "Gnd_2") (pintype "passive"))
      (node (ref "TP9") (pin "2") (pinfunction "Gnd_2") (pintype "passive"))
      (node (ref "U1") (pin "1") (pinfunction "GND_1") (pintype "passive"))
      (node (ref "U2") (pin "21") (pinfunction "GND_21") (pintype "power_in"))
      (node (ref "U2") (pin "3") (pinfunction "GND_3") (pintype "power_in"))
      (node (ref "U2") (pin "5") (pinfunction "GND_5") (pintype "power_in"))
      (node (ref "Y1") (pin "2") (pinfunction "GND_2") (pintype "passive"))
      (node (ref "Y1") (pin "4") (pinfunction "GND_4") (pintype "passive"))
      (node (ref "Y2") (pin "2") (pinfunction "GND_2") (pintype "passive"))
      (node (ref "Y2") (pin "4") (pinfunction "GND_4") (pintype "passive"))
    )
    (net (code "35") (name "Net-(LED1-Pad2)") (class "Default")
      (node (ref "LED1") (pin "2") (pinfunction "2_2") (pintype "passive"))
      (node (ref "R9") (pin "1") (pinfunction "1_1") (pintype "passive"))
    )
    (net (code "36") (name "Net-(LED2-Pad2)") (class "Default")
      (node (ref "LED2") (pin "2") (pinfunction "2_2") (pintype "passive"))
      (node (ref "R3") (pin "2") (pinfunction "2_2") (pintype "passive"))
    )
    (net (code "37") (name "Net-(LED3-Pad2)") (class "Default")
      (node (ref "LED3") (pin "2") (pinfunction "2_2") (pintype "passive"))
      (node (ref "R2") (pin "2") (pinfunction "2_2") (pintype "passive"))
    )
    (net (code "38") (name "Net-(LED4-Pad2)") (class "Default")
      (node (ref "LED4") (pin "2") (pinfunction "2_2") (pintype "passive"))
      (node (ref "R10") (pin "1") (pinfunction "1_1") (pintype "passive"))
    )
    (net (code "39") (name "Net-(LED5-Pad2)") (class "Default")
      (node (ref "LED5") (pin "2") (pinfunction "2_2") (pintype "passive"))
      (node (ref "R11") (pin "1") (pinfunction "1_1") (pintype "passive"))
    )
    (net (code "40") (name "Net-(TP10-Sgn)") (class "Default")
      (node (ref "R1") (pin "1") (pinfunction "1_1") (pintype "passive"))
      (node (ref "SW1") (pin "2") (pinfunction "2_2") (pintype "passive"))
      (node (ref "TP10") (pin "1") (pinfunction "Sgn_1") (pintype "passive"))
    )
    (net (code "41") (name "Net-(U1-RXD)") (class "Default")
      (node (ref "R5") (pin "2") (pinfunction "2_2") (pintype "passive"))
      (node (ref "U1") (pin "3") (pinfunction "RXD_3") (pintype "passive"))
    )
    (net (code "42") (name "Net-(U1-TXD)") (class "Default")
      (node (ref "R4") (pin "2") (pinfunction "2_2") (pintype "passive"))
      (node (ref "U1") (pin "2") (pinfunction "TXD_2") (pintype "passive"))
    )
    (net (code "43") (name "Net-(U1-V3)") (class "Default")
      (node (ref "C4") (pin "1") (pinfunction "1_1") (pintype "passive"))
      (node (ref "U1") (pin "4") (pinfunction "V3_4") (pintype "passive"))
    )
    (net (code "44") (name "Net-(U2-AVCC)") (class "Default")
      (node (ref "C12") (pin "1") (pinfunction "1_1") (pintype "passive"))
      (node (ref "L1") (pin "1") (pinfunction "1_1") (pintype "passive"))
      (node (ref "U2") (pin "18") (pinfunction "AVCC_18") (pintype "power_in"))
    )
    (net (code "45") (name "USB_VCC") (class "Default")
      (node (ref "D1") (pin "5") (pinfunction "VCC_5") (pintype "passive"))
      (node (ref "J1") (pin "1") (pinfunction "VBUS_1") (pintype "passive"))
      (node (ref "LED1") (pin "1") (pinfunction "1_1") (pintype "passive"))
      (node (ref "SW1") (pin "3") (pinfunction "3_3") (pintype "passive"))
    )
    (net (code "46") (name "unconnected-(D1-IO-3-Pad4)") (class "Default")
      (node (ref "D1") (pin "4") (pinfunction "IO-3_4") (pintype "passive"))
    )
    (net (code "47") (name "unconnected-(D1-IO-4-Pad6)") (class "Default")
      (node (ref "D1") (pin "6") (pinfunction "IO-4_6") (pintype "passive"))
    )
    (net (code "48") (name "unconnected-(J1-ID-Pad4)") (class "Default")
      (node (ref "J1") (pin "4") (pinfunction "ID_4") (pintype "passive"))
    )
    (net (code "49") (name "unconnected-(J3-NC-Pad1)") (class "Default")
      (node (ref "J3") (pin "1") (pinfunction "NC_1") (pintype "passive"))
    )
    (net (code "50") (name "unconnected-(U1-CTS#-Pad9)") (class "Default")
      (node (ref "U1") (pin "9") (pinfunction "CTS#_9") (pintype "passive"))
    )
    (net (code "51") (name "unconnected-(U1-DCD#-Pad12)") (class "Default")
      (node (ref "U1") (pin "12") (pinfunction "DCD#_12") (pintype "passive"))
    )
    (net (code "52") (name "unconnected-(U1-DSR#-Pad10)") (class "Default")
      (node (ref "U1") (pin "10") (pinfunction "DSR#_10") (pintype "passive"))
    )
    (net (code "53") (name "unconnected-(U1-RI#-Pad11)") (class "Default")
      (node (ref "U1") (pin "11") (pinfunction "RI#_11") (pintype "passive"))
    )
    (net (code "54") (name "unconnected-(U1-RS232-Pad15)") (class "Default")
      (node (ref "U1") (pin "15") (pinfunction "RS232_15") (pintype "passive"))
    )
    (net (code "55") (name "unconnected-(U1-RTS#-Pad14)") (class "Default")
      (node (ref "U1") (pin "14") (pinfunction "RTS#_14") (pintype "passive"))
    )
    (net (code "56") (name "unconnected-(U2-ADC6-Pad19)") (class "Default")
      (node (ref "U2") (pin "19") (pinfunction "ADC6_19") (pintype "bidirectional"))
    )
    (net (code "57") (name "unconnected-(U2-ADC7-Pad22)") (class "Default")
      (node (ref "U2") (pin "22") (pinfunction "ADC7_22") (pintype "bidirectional"))
    )
  )
)
